# v1_0.net
KiCad netlist of a schematic drawn in Altium Designer
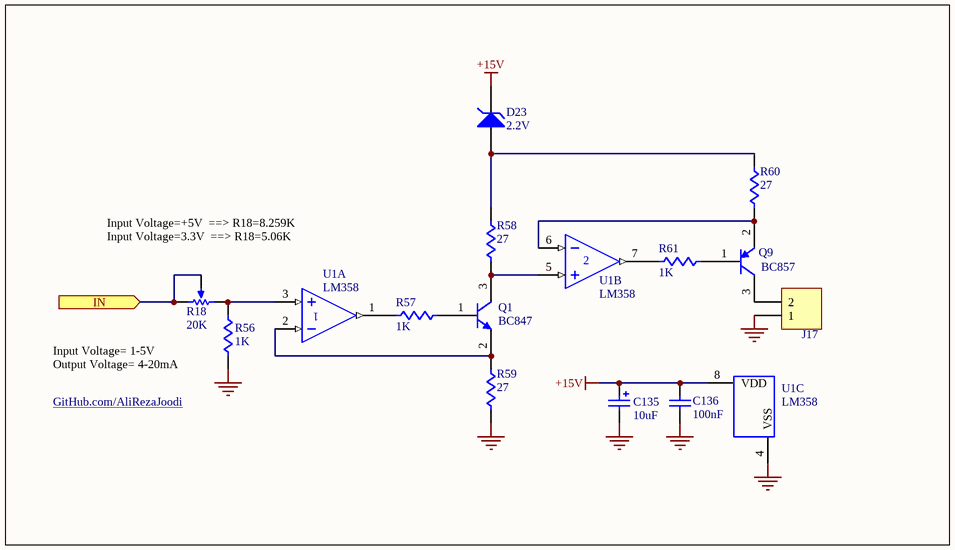
[diagram p0: v1.0.SchDoc]

(export (version "E")
  (design (tool "Eeschema 10.0.6"))
  (components
    (comp (ref "C135")
      (value "10uF")
      (footprint "Cap_B")
      (description "Polarized Capacitor (Radial)")
      (fields
        (field (name "MANUFACTURER") "Generic Components")
        (field (name "Comment") "Capacitor")
        (field (name "PUBLISHER") "Altium Limited")
      )
      (libsource (lib "Miscellaneous Devices") (part "Cap Pol1"))
    )
    (comp (ref "C136")
      (value "100nF")
      (footprint "0805")
      (description "Capacitor")
      (fields
        (field (name "MANUFACTURER") "Generic Components")
        (field (name "Comment") "Cap")
        (field (name "PUBLISHER") "Altium Limited")
      )
      (libsource (lib "Miscellaneous Devices") (part "Cap"))
    )
    (comp (ref "D23")
      (value "2.2V")
      (footprint "MELF-D3516-1406")
      (description "Zener Diode")
      (fields
        (field (name "MANUFACTURER") "Generic Components")
        (field (name "Comment") "LED")
        (field (name "PUBLISHER") "Altium Limited")
      )
      (libsource (lib "Miscellaneous Devices") (part "D Zener"))
    )
    (comp (ref "J17")
      (value "J17")
      (footprint "Fonics_2PIN_1")
      (description "Header, 2-Pin")
      (fields (field (name "PUBLISHER") "Altium Limited"))
      (libsource (lib "Miscellaneous Connectors") (part "Header 2"))
    )
    (comp (ref "Q1")
      (value "BC847")
      (footprint "SOT23-3N")
      (description "Silicon Bipolar Transistor")
      (fields (field (name "Comment") "NPN"))
      (libsource (lib "my Libraries") (part "BC847"))
    )
    (comp (ref "Q9")
      (value "BC857")
      (footprint "SOT23-3N")
      (description "Silicon Bipolar Transistor")
      (fields (field (name "Comment") "Q"))
      (libsource (lib "my Libraries") (part "BC857"))
    )
    (comp (ref "R18")
      (value "20K")
      (footprint "VR4_")
      (description "Potentiometer")
      (fields
        (field (name "MANUFACTURER") "Generic Components")
        (field (name "Comment") "RES")
        (field (name "PUBLISHER") "Altium Limited")
      )
      (libsource (lib "my Libraries") (part "RPot1"))
    )
    (comp (ref "R56")
      (value "1K")
      (footprint "0805")
      (description "Resistor")
      (fields
        (field (name "MANUFACTURER") "Generic Components")
        (field (name "Comment") "RES")
        (field (name "PUBLISHER") "Altium Limited")
      )
      (libsource (lib "Miscellaneous Devices") (part "Res1"))
    )
    (comp (ref "R57")
      (value "1K")
      (footprint "0805")
      (description "Resistor")
      (fields
        (field (name "MANUFACTURER") "Generic Components")
        (field (name "Comment") "RES")
        (field (name "PUBLISHER") "Altium Limited")
      )
      (libsource (lib "Miscellaneous Devices") (part "Res1"))
    )
    (comp (ref "R58")
      (value "27")
      (footprint "0805")
      (description "Resistor")
      (fields
        (field (name "MANUFACTURER") "Generic Components")
        (field (name "Comment") "R58")
        (field (name "PUBLISHER") "Altium Limited")
      )
      (libsource (lib "Miscellaneous Devices") (part "Res1"))
    )
    (comp (ref "R59")
      (value "27")
      (footprint "0805")
      (description "Resistor")
      (fields
        (field (name "MANUFACTURER") "Generic Components")
        (field (name "Comment") "R59")
        (field (name "PUBLISHER") "Altium Limited")
      )
      (libsource (lib "Miscellaneous Devices") (part "Res1"))
    )
    (comp (ref "R60")
      (value "27")
      (footprint "0805")
      (description "Resistor")
      (fields
        (field (name "MANUFACTURER") "Generic Components")
        (field (name "Comment") "R60")
        (field (name "PUBLISHER") "Altium Limited")
      )
      (libsource (lib "Miscellaneous Devices") (part "Res1"))
    )
    (comp (ref "R61")
      (value "1K")
      (footprint "0805")
      (description "Resistor")
      (fields
        (field (name "MANUFACTURER") "Generic Components")
        (field (name "Comment") "R61")
        (field (name "PUBLISHER") "Altium Limited")
      )
      (libsource (lib "Miscellaneous Devices") (part "Res1"))
    )
    (comp (ref "U1")
      (value "LM358")
      (footprint "SOP127P636-8N")
      (description "Dual Low-Power Operational Amplifier")
      (fields (field (name "PUBLISHER") "Altium Limited"))
      (libsource (lib "my Libraries") (part "LM358"))
    )
  )
  (nets
    (net (code "1") (name "+15V") (class "Default")
      (node (ref "C135") (pin "1") (pinfunction "1_1") (pintype "passive"))
      (node (ref "C136") (pin "2") (pinfunction "2_2") (pintype "passive"))
      (node (ref "D23") (pin "2") (pinfunction "K_2") (pintype "passive"))
      (node (ref "U1") (pin "8") (pinfunction "VDD_8") (pintype "passive"))
    )
    (net (code "2") (name "/IN") (class "Default")
      (node (ref "R18") (pin "2") (pinfunction "BOT_2") (pintype "passive"))
      (node (ref "R18") (pin "3") (pinfunction "TAP_3") (pintype "passive"))
    )
    (net (code "3") (name "GND") (class "Default")
      (node (ref "C135") (pin "2") (pinfunction "2_2") (pintype "passive"))
      (node (ref "C136") (pin "1") (pinfunction "1_1") (pintype "passive"))
      (node (ref "J17") (pin "1") (pinfunction "1_1") (pintype "passive"))
      (node (ref "R56") (pin "2") (pinfunction "2_2") (pintype "passive"))
      (node (ref "R59") (pin "1") (pinfunction "1_1") (pintype "passive"))
      (node (ref "U1") (pin "4") (pinfunction "VSS_4") (pintype "power_in"))
    )
    (net (code "4") (name "Net-(D23-A)") (class "Default")
      (node (ref "D23") (pin "1") (pinfunction "A_1") (pintype "passive"))
      (node (ref "R58") (pin "2") (pinfunction "2_2") (pintype "passive"))
      (node (ref "R60") (pin "2") (pinfunction "2_2") (pintype "passive"))
    )
    (net (code "5") (name "Net-(Q1-B)") (class "Default")
      (node (ref "Q1") (pin "1") (pinfunction "B_1") (pintype "passive"))
      (node (ref "R57") (pin "2") (pinfunction "2_2") (pintype "passive"))
    )
    (net (code "6") (name "Net-(Q1-C)") (class "Default")
      (node (ref "Q1") (pin "3") (pinfunction "C_3") (pintype "passive"))
      (node (ref "R58") (pin "1") (pinfunction "1_1") (pintype "passive"))
      (node (ref "U1") (pin "5") (pinfunction "IN+_5") (pintype "input"))
    )
    (net (code "7") (name "Net-(Q1-E)") (class "Default")
      (node (ref "Q1") (pin "2") (pinfunction "E_2") (pintype "passive"))
      (node (ref "R59") (pin "2") (pinfunction "2_2") (pintype "passive"))
      (node (ref "U1") (pin "2") (pinfunction "IN-_2") (pintype "input"))
    )
    (net (code "8") (name "Net-(Q9-B)") (class "Default")
      (node (ref "Q9") (pin "1") (pinfunction "B_1") (pintype "passive"))
      (node (ref "R61") (pin "2") (pinfunction "2_2") (pintype "passive"))
    )
    (net (code "9") (name "Net-(Q9-C)") (class "Default")
      (node (ref "J17") (pin "2") (pinfunction "2_2") (pintype "passive"))
      (node (ref "Q9") (pin "3") (pinfunction "C_3") (pintype "passive"))
    )
    (net (code "10") (name "Net-(Q9-E)") (class "Default")
      (node (ref "Q9") (pin "2") (pinfunction "E_2") (pintype "passive"))
      (node (ref "R60") (pin "1") (pinfunction "1_1") (pintype "passive"))
      (node (ref "U1") (pin "6") (pinfunction "IN-_6") (pintype "input"))
    )
    (net (code "11") (name "Net-(R18-TOP)") (class "Default")
      (node (ref "R18") (pin "1") (pinfunction "TOP_1") (pintype "passive"))
      (node (ref "R56") (pin "1") (pinfunction "1_1") (pintype "passive"))
      (node (ref "U1") (pin "3") (pinfunction "IN+_3") (pintype "input"))
    )
    (net (code "12") (name "Net-(U1A-OUT)") (class "Default")
      (node (ref "R57") (pin "1") (pinfunction "1_1") (pintype "passive"))
      (node (ref "U1") (pin "1") (pinfunction "OUT_1") (pintype "output"))
    )
    (net (code "13") (name "Net-(U1B-OUT)") (class "Default")
      (node (ref "R61") (pin "1") (pinfunction "1_1") (pintype "passive"))
      (node (ref "U1") (pin "7") (pinfunction "OUT_7") (pintype "output"))
    )
  )
)
